# FPC2DFPC.net
KiCad netlist of a schematic drawn in Altium Designer
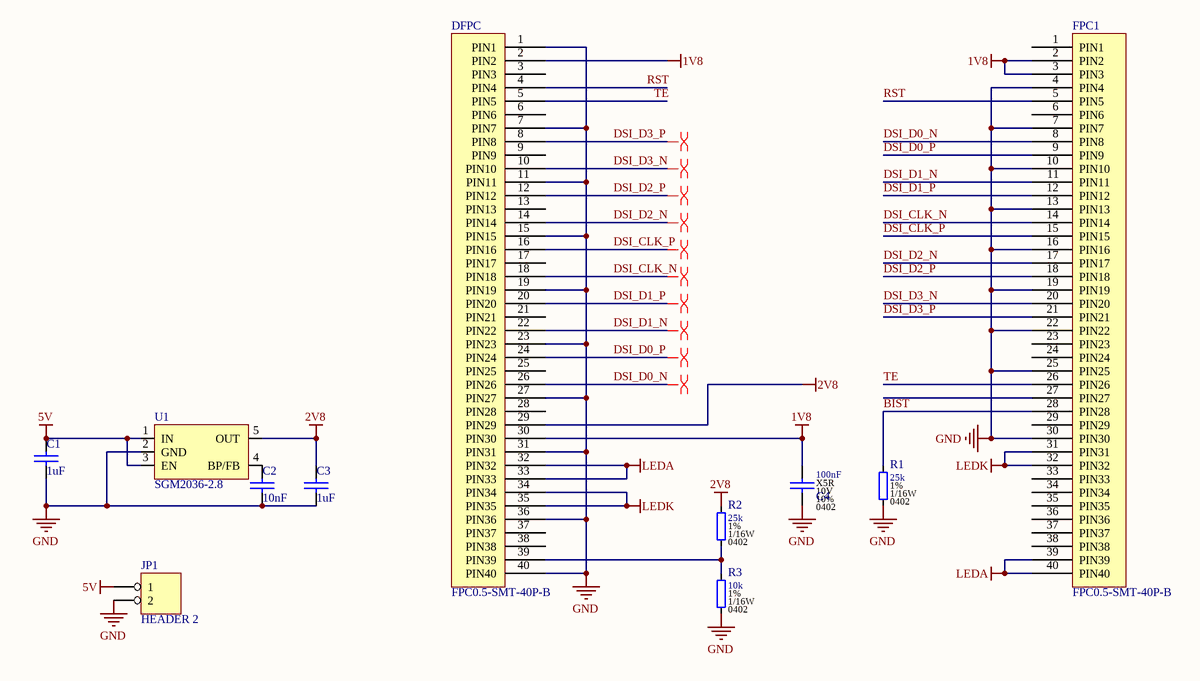
[diagram p0: FPC2DFPC.SchDoc]

(export (version "E")
  (design (tool "Eeschema 10.0.6"))
  (components
    (comp (ref "C1")
      (value "1uF")
      (footprint "0402_CAP_SMT")
      (description "陶瓷电容")
      (libsource (lib "ZX_MyLib") (part "CAP"))
    )
    (comp (ref "C2")
      (value "10nF")
      (footprint "0402_CAP_SMT")
      (description "陶瓷电容")
      (libsource (lib "ZX_MyLib") (part "CAP"))
    )
    (comp (ref "C3")
      (value "1uF")
      (footprint "0402_CAP_SMT")
      (description "陶瓷电容")
      (libsource (lib "ZX_MyLib") (part "CAP"))
    )
    (comp (ref "C4")
      (value "100nF")
      (footprint "0402")
      (description "陶瓷电容")
      (fields
        (field (name "DIELECTRIC") "X5R")
        (field (name "VOLTAGE") "10V")
        (field (name "TOLERANCE") "10%")
        (field (name "Comment") "CAP")
      )
      (libsource (lib "") (part "CAP_1"))
    )
    (comp (ref "DFPC")
      (value "FPC0.5-SMT-40P-B")
      (footprint "DFPC")
      (libsource (lib "") (part "FPC0.5-SMT-40P-B_1"))
    )
    (comp (ref "FPC1")
      (value "FPC0.5-SMT-40P-B")
      (footprint "FPC0.5-SMT-40P-B")
      (libsource (lib "ZX_MyLib") (part "FPC0.5-SMT-40P-B"))
    )
    (comp (ref "JP1")
      (value "HEADER 2")
      (footprint "2PIN_125MM_SMT_VERTICAL")
      (libsource (lib "ZX_MyLib") (part "HEADER 2"))
    )
    (comp (ref "R1")
      (value "25k")
      (footprint "0402")
      (description "贴片电阻")
      (fields (field (name "TOLERANCE") "1%") (field (name "WATTAGE") "1/16W") (field (name "Comment") "RES"))
      (libsource (lib "ZX_MyLib") (part "RES"))
    )
    (comp (ref "R2")
      (value "25k")
      (footprint "0402")
      (description "贴片电阻")
      (fields (field (name "TOLERANCE") "1%") (field (name "WATTAGE") "1/16W") (field (name "Comment") "RES"))
      (libsource (lib "ZX_MyLib") (part "RES"))
    )
    (comp (ref "R3")
      (value "10k")
      (footprint "0402")
      (description "贴片电阻")
      (fields (field (name "TOLERANCE") "1%") (field (name "WATTAGE") "1/16W") (field (name "Comment") "RES"))
      (libsource (lib "ZX_MyLib") (part "RES"))
    )
    (comp (ref "U1")
      (value "SGM2036-2.8")
      (footprint "SOT23-5")
      (description "LDO")
      (libsource (lib "ZX_MyLib") (part "SGM2036"))
    )
  )
  (nets
    (net (code "1") (name "/BIST") (class "Default")
      (node (ref "FPC1") (pin "28") (pinfunction "PIN28_28") (pintype "passive"))
      (node (ref "R1") (pin "1") (pinfunction "1_1") (pintype "passive"))
    )
    (net (code "2") (name "/DSI_CLK_N") (class "Default")
      (node (ref "DFPC") (pin "18") (pinfunction "PIN18_18") (pintype "passive"))
      (node (ref "FPC1") (pin "14") (pinfunction "PIN14_14") (pintype "passive"))
    )
    (net (code "3") (name "/DSI_CLK_P") (class "Default")
      (node (ref "DFPC") (pin "16") (pinfunction "PIN16_16") (pintype "passive"))
      (node (ref "FPC1") (pin "15") (pinfunction "PIN15_15") (pintype "passive"))
    )
    (net (code "4") (name "/DSI_D0_N") (class "Default")
      (node (ref "DFPC") (pin "26") (pinfunction "PIN26_26") (pintype "passive"))
      (node (ref "FPC1") (pin "8") (pinfunction "PIN8_8") (pintype "passive"))
    )
    (net (code "5") (name "/DSI_D0_P") (class "Default")
      (node (ref "DFPC") (pin "24") (pinfunction "PIN24_24") (pintype "passive"))
      (node (ref "FPC1") (pin "9") (pinfunction "PIN9_9") (pintype "passive"))
    )
    (net (code "6") (name "/DSI_D1_N") (class "Default")
      (node (ref "DFPC") (pin "22") (pinfunction "PIN22_22") (pintype "passive"))
      (node (ref "FPC1") (pin "11") (pinfunction "PIN11_11") (pintype "passive"))
    )
    (net (code "7") (name "/DSI_D1_P") (class "Default")
      (node (ref "DFPC") (pin "20") (pinfunction "PIN20_20") (pintype "passive"))
      (node (ref "FPC1") (pin "12") (pinfunction "PIN12_12") (pintype "passive"))
    )
    (net (code "8") (name "/DSI_D2_N") (class "Default")
      (node (ref "DFPC") (pin "14") (pinfunction "PIN14_14") (pintype "passive"))
      (node (ref "FPC1") (pin "17") (pinfunction "PIN17_17") (pintype "passive"))
    )
    (net (code "9") (name "/DSI_D2_P") (class "Default")
      (node (ref "DFPC") (pin "12") (pinfunction "PIN12_12") (pintype "passive"))
      (node (ref "FPC1") (pin "18") (pinfunction "PIN18_18") (pintype "passive"))
    )
    (net (code "10") (name "/DSI_D3_N") (class "Default")
      (node (ref "DFPC") (pin "10") (pinfunction "PIN10_10") (pintype "passive"))
      (node (ref "FPC1") (pin "20") (pinfunction "PIN20_20") (pintype "passive"))
    )
    (net (code "11") (name "/DSI_D3_P") (class "Default")
      (node (ref "DFPC") (pin "8") (pinfunction "PIN8_8") (pintype "passive"))
      (node (ref "FPC1") (pin "21") (pinfunction "PIN21_21") (pintype "passive"))
    )
    (net (code "12") (name "/RST") (class "Default")
      (node (ref "DFPC") (pin "4") (pinfunction "PIN4_4") (pintype "passive"))
      (node (ref "FPC1") (pin "5") (pinfunction "PIN5_5") (pintype "passive"))
    )
    (net (code "13") (name "/TE") (class "Default")
      (node (ref "DFPC") (pin "5") (pinfunction "PIN5_5") (pintype "passive"))
      (node (ref "FPC1") (pin "26") (pinfunction "PIN26_26") (pintype "passive"))
    )
    (net (code "14") (name "1V8") (class "Default")
      (node (ref "C4") (pin "1") (pinfunction "1_1") (pintype "passive"))
      (node (ref "DFPC") (pin "2") (pinfunction "PIN2_2") (pintype "passive"))
      (node (ref "DFPC") (pin "30") (pinfunction "PIN30_30") (pintype "passive"))
      (node (ref "FPC1") (pin "2") (pinfunction "PIN2_2") (pintype "passive"))
      (node (ref "FPC1") (pin "3") (pinfunction "PIN3_3") (pintype "passive"))
    )
    (net (code "15") (name "2V8") (class "Default")
      (node (ref "C3") (pin "1") (pinfunction "1_1") (pintype "passive"))
      (node (ref "DFPC") (pin "29") (pinfunction "PIN29_29") (pintype "passive"))
      (node (ref "R2") (pin "1") (pinfunction "1_1") (pintype "passive"))
      (node (ref "U1") (pin "5") (pinfunction "OUT_5") (pintype "passive"))
    )
    (net (code "16") (name "5V") (class "Default")
      (node (ref "C1") (pin "1") (pinfunction "1_1") (pintype "passive"))
      (node (ref "JP1") (pin "1") (pinfunction "1_1") (pintype "passive"))
      (node (ref "U1") (pin "1") (pinfunction "IN_1") (pintype "passive"))
      (node (ref "U1") (pin "3") (pinfunction "EN_3") (pintype "passive"))
    )
    (net (code "17") (name "GND") (class "Default")
      (node (ref "C1") (pin "2") (pinfunction "2_2") (pintype "passive"))
      (node (ref "C2") (pin "2") (pinfunction "2_2") (pintype "passive"))
      (node (ref "C3") (pin "2") (pinfunction "2_2") (pintype "passive"))
      (node (ref "C4") (pin "2") (pinfunction "2_2") (pintype "passive"))
      (node (ref "DFPC") (pin "1") (pinfunction "PIN1_1") (pintype "passive"))
      (node (ref "DFPC") (pin "11") (pinfunction "PIN11_11") (pintype "passive"))
      (node (ref "DFPC") (pin "15") (pinfunction "PIN15_15") (pintype "passive"))
      (node (ref "DFPC") (pin "19") (pinfunction "PIN19_19") (pintype "passive"))
      (node (ref "DFPC") (pin "23") (pinfunction "PIN23_23") (pintype "passive"))
      (node (ref "DFPC") (pin "27") (pinfunction "PIN27_27") (pintype "passive"))
      (node (ref "DFPC") (pin "31") (pinfunction "PIN31_31") (pintype "passive"))
      (node (ref "DFPC") (pin "36") (pinfunction "PIN36_36") (pintype "passive"))
      (node (ref "DFPC") (pin "40") (pinfunction "PIN40_40") (pintype "passive"))
      (node (ref "DFPC") (pin "7") (pinfunction "PIN7_7") (pintype "passive"))
      (node (ref "FPC1") (pin "10") (pinfunction "PIN10_10") (pintype "passive"))
      (node (ref "FPC1") (pin "13") (pinfunction "PIN13_13") (pintype "passive"))
      (node (ref "FPC1") (pin "16") (pinfunction "PIN16_16") (pintype "passive"))
      (node (ref "FPC1") (pin "19") (pinfunction "PIN19_19") (pintype "passive"))
      (node (ref "FPC1") (pin "22") (pinfunction "PIN22_22") (pintype "passive"))
      (node (ref "FPC1") (pin "25") (pinfunction "PIN25_25") (pintype "passive"))
      (node (ref "FPC1") (pin "30") (pinfunction "PIN30_30") (pintype "passive"))
      (node (ref "FPC1") (pin "4") (pinfunction "PIN4_4") (pintype "passive"))
      (node (ref "FPC1") (pin "7") (pinfunction "PIN7_7") (pintype "passive"))
      (node (ref "JP1") (pin "2") (pinfunction "2_2") (pintype "passive"))
      (node (ref "R1") (pin "2") (pinfunction "2_2") (pintype "passive"))
      (node (ref "R3") (pin "2") (pinfunction "2_2") (pintype "passive"))
      (node (ref "U1") (pin "2") (pinfunction "GND_2") (pintype "passive"))
    )
    (net (code "18") (name "LEDA") (class "Default")
      (node (ref "DFPC") (pin "32") (pinfunction "PIN32_32") (pintype "passive"))
      (node (ref "DFPC") (pin "33") (pinfunction "PIN33_33") (pintype "passive"))
      (node (ref "FPC1") (pin "39") (pinfunction "PIN39_39") (pintype "passive"))
      (node (ref "FPC1") (pin "40") (pinfunction "PIN40_40") (pintype "passive"))
    )
    (net (code "19") (name "LEDK") (class "Default")
      (node (ref "DFPC") (pin "34") (pinfunction "PIN34_34") (pintype "passive"))
      (node (ref "DFPC") (pin "35") (pinfunction "PIN35_35") (pintype "passive"))
      (node (ref "FPC1") (pin "31") (pinfunction "PIN31_31") (pintype "passive"))
      (node (ref "FPC1") (pin "32") (pinfunction "PIN32_32") (pintype "passive"))
    )
    (net (code "20") (name "Net-(DFPC-PIN39)") (class "Default")
      (node (ref "DFPC") (pin "39") (pinfunction "PIN39_39") (pintype "passive"))
      (node (ref "R2") (pin "2") (pinfunction "2_2") (pintype "passive"))
      (node (ref "R3") (pin "1") (pinfunction "1_1") (pintype "passive"))
    )
    (net (code "21") (name "Net-(U1-BP{slash}FB)") (class "Default")
      (node (ref "C2") (pin "1") (pinfunction "1_1") (pintype "passive"))
      (node (ref "U1") (pin "4") (pinfunction "BP/FB_4") (pintype "passive"))
    )
    (net (code "22") (name "unconnected-(DFPC-PIN3-Pad3)") (class "Default")
      (node (ref "DFPC") (pin "3") (pinfunction "PIN3_3") (pintype "passive"))
    )
    (net (code "23") (name "unconnected-(DFPC-PIN6-Pad6)") (class "Default")
      (node (ref "DFPC") (pin "6") (pinfunction "PIN6_6") (pintype "passive"))
    )
    (net (code "24") (name "unconnected-(DFPC-PIN9-Pad9)") (class "Default")
      (node (ref "DFPC") (pin "9") (pinfunction "PIN9_9") (pintype "passive"))
    )
    (net (code "25") (name "unconnected-(DFPC-PIN13-Pad13)") (class "Default")
      (node (ref "DFPC") (pin "13") (pinfunction "PIN13_13") (pintype "passive"))
    )
    (net (code "26") (name "unconnected-(DFPC-PIN17-Pad17)") (class "Default")
      (node (ref "DFPC") (pin "17") (pinfunction "PIN17_17") (pintype "passive"))
    )
    (net (code "27") (name "unconnected-(DFPC-PIN21-Pad21)") (class "Default")
      (node (ref "DFPC") (pin "21") (pinfunction "PIN21_21") (pintype "passive"))
    )
    (net (code "28") (name "unconnected-(DFPC-PIN25-Pad25)") (class "Default")
      (node (ref "DFPC") (pin "25") (pinfunction "PIN25_25") (pintype "passive"))
    )
    (net (code "29") (name "unconnected-(DFPC-PIN28-Pad28)") (class "Default")
      (node (ref "DFPC") (pin "28") (pinfunction "PIN28_28") (pintype "passive"))
    )
    (net (code "30") (name "unconnected-(DFPC-PIN37-Pad37)") (class "Default")
      (node (ref "DFPC") (pin "37") (pinfunction "PIN37_37") (pintype "passive"))
    )
    (net (code "31") (name "unconnected-(DFPC-PIN38-Pad38)") (class "Default")
      (node (ref "DFPC") (pin "38") (pinfunction "PIN38_38") (pintype "passive"))
    )
    (net (code "32") (name "unconnected-(FPC1-PIN1-Pad1)") (class "Default")
      (node (ref "FPC1") (pin "1") (pinfunction "PIN1_1") (pintype "passive"))
    )
    (net (code "33") (name "unconnected-(FPC1-PIN6-Pad6)") (class "Default")
      (node (ref "FPC1") (pin "6") (pinfunction "PIN6_6") (pintype "passive"))
    )
    (net (code "34") (name "unconnected-(FPC1-PIN23-Pad23)") (class "Default")
      (node (ref "FPC1") (pin "23") (pinfunction "PIN23_23") (pintype "passive"))
    )
    (net (code "35") (name "unconnected-(FPC1-PIN24-Pad24)") (class "Default")
      (node (ref "FPC1") (pin "24") (pinfunction "PIN24_24") (pintype "passive"))
    )
    (net (code "36") (name "unconnected-(FPC1-PIN27-Pad27)") (class "Default")
      (node (ref "FPC1") (pin "27") (pinfunction "PIN27_27") (pintype "passive"))
    )
    (net (code "37") (name "unconnected-(FPC1-PIN29-Pad29)") (class "Default")
      (node (ref "FPC1") (pin "29") (pinfunction "PIN29_29") (pintype "passive"))
    )
    (net (code "38") (name "unconnected-(FPC1-PIN33-Pad33)") (class "Default")
      (node (ref "FPC1") (pin "33") (pinfunction "PIN33_33") (pintype "passive"))
    )
    (net (code "39") (name "unconnected-(FPC1-PIN34-Pad34)") (class "Default")
      (node (ref "FPC1") (pin "34") (pinfunction "PIN34_34") (pintype "passive"))
    )
    (net (code "40") (name "unconnected-(FPC1-PIN35-Pad35)") (class "Default")
      (node (ref "FPC1") (pin "35") (pinfunction "PIN35_35") (pintype "passive"))
    )
    (net (code "41") (name "unconnected-(FPC1-PIN36-Pad36)") (class "Default")
      (node (ref "FPC1") (pin "36") (pinfunction "PIN36_36") (pintype "passive"))
    )
    (net (code "42") (name "unconnected-(FPC1-PIN37-Pad37)") (class "Default")
      (node (ref "FPC1") (pin "37") (pinfunction "PIN37_37") (pintype "passive"))
    )
    (net (code "43") (name "unconnected-(FPC1-PIN38-Pad38)") (class "Default")
      (node (ref "FPC1") (pin "38") (pinfunction "PIN38_38") (pintype "passive"))
    )
  )
)
